# layout.net
KiCad netlist of a schematic drawn in EAGLE
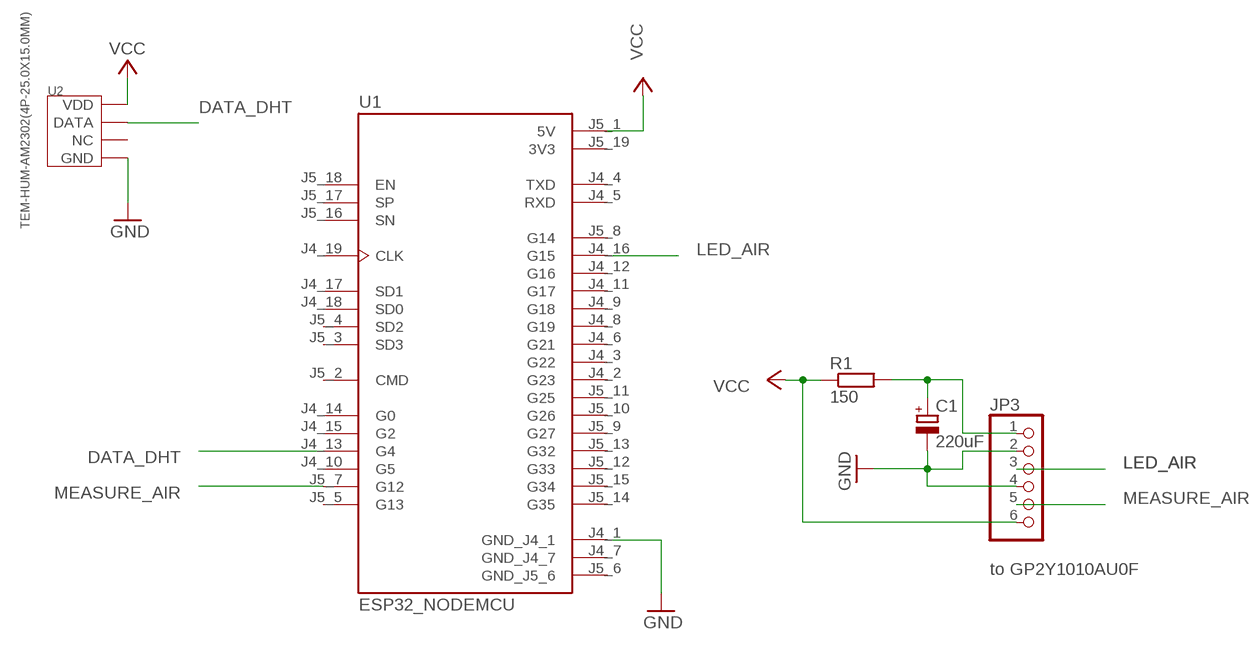
[diagram p0: schematic, sheet 1]

(export (version "E")
  (design (tool "Eeschema 10.0.6"))
  (components
    (comp (ref "C1")
      (value "220uF")
      (footprint "eagle-import:E2-5")
      (libsource (lib "eagle-import") (part "CPOL-EUE2-5"))
    )
    (comp (ref "JP3")
      (value "to GP2Y1010AU0F")
      (footprint "eagle-import:1X06")
      (libsource (lib "eagle-import") (part "PINHD-1X6"))
    )
    (comp (ref "R1")
      (value "150")
      (footprint "eagle-import:0204_7")
      (libsource (lib "eagle-import") (part "R-EU_0204/7"))
    )
    (comp (ref "U1")
      (value "ESP32_NODEMCU")
      (footprint "eagle-import:MODULE_ESP32_NODEMCU")
      (fields (field (name "MF") "Espressif Systems") (field (name "MP") "ESP32 NodeMCU"))
      (libsource (lib "eagle-import") (part "ESP32_NODEMCU"))
    )
    (comp (ref "U2")
      (value "TEM-HUM-AM2302(4P-25.0X15.0MM)")
      (footprint "eagle-import:SNR4-2.54-25.0X15.0X7.0MM")
      (fields (field (name "MF") "MCM Electronics") (field (name "MP") "AM2302"))
      (libsource (lib "eagle-import") (part "TEM-HUM-AM2302(4P-25.0X15.0MM)"))
    )
  )
  (nets
    (net (code "1") (name "/3V3") (class "Default")
      (node (ref "U1") (pin "J5_19") (pinfunction "3V3_J5_19") (pintype "power_in"))
    )
    (net (code "2") (name "/DATA_DHT") (class "Default")
      (node (ref "U1") (pin "J4_13") (pinfunction "G4_J4_13") (pintype "bidirectional"))
      (node (ref "U2") (pin "P$2") (pinfunction "DATA_P$2") (pintype "bidirectional"))
    )
    (net (code "3") (name "/GND_J4_7") (class "Default")
      (node (ref "U1") (pin "J4_7") (pinfunction "GND_J4_7_J4_7") (pintype "power_in"))
    )
    (net (code "4") (name "/GND_J5_6") (class "Default")
      (node (ref "U1") (pin "J5_6") (pinfunction "GND_J5_6_J5_6") (pintype "power_in"))
    )
    (net (code "5") (name "/LED_AIR") (class "Default")
      (node (ref "JP3") (pin "3") (pinfunction "3_3") (pintype "passive"))
      (node (ref "U1") (pin "J4_16") (pinfunction "G15_J4_16") (pintype "bidirectional"))
    )
    (net (code "6") (name "/MEASURE_AIR") (class "Default")
      (node (ref "JP3") (pin "5") (pinfunction "5_5") (pintype "passive"))
      (node (ref "U1") (pin "J5_7") (pinfunction "G12_J5_7") (pintype "bidirectional"))
    )
    (net (code "7") (name "GND") (class "Default")
      (node (ref "C1") (pin "-") (pinfunction "-_-") (pintype "passive"))
      (node (ref "JP3") (pin "2") (pinfunction "2_2") (pintype "passive"))
      (node (ref "JP3") (pin "4") (pinfunction "4_4") (pintype "passive"))
      (node (ref "U1") (pin "J4_1") (pinfunction "GND_J4_1_J4_1") (pintype "power_in"))
      (node (ref "U2") (pin "P$4") (pinfunction "GND_P$4") (pintype "power_in"))
    )
    (net (code "8") (name "Net-(C1-Pad+)") (class "Default")
      (node (ref "C1") (pin "+") (pinfunction "+_+") (pintype "passive"))
      (node (ref "JP3") (pin "1") (pinfunction "1_1") (pintype "passive"))
      (node (ref "R1") (pin "2") (pinfunction "2_2") (pintype "passive"))
    )
    (net (code "9") (name "VCC") (class "Default")
      (node (ref "JP3") (pin "6") (pinfunction "6_6") (pintype "passive"))
      (node (ref "R1") (pin "1") (pinfunction "1_1") (pintype "passive"))
      (node (ref "U1") (pin "J5_1") (pinfunction "5V_J5_1") (pintype "power_in"))
      (node (ref "U2") (pin "P$1") (pinfunction "VDD_P$1") (pintype "power_in"))
    )
    (net (code "10") (name "unconnected-(U1-CLK-PadJ4_19)") (class "Default")
      (node (ref "U1") (pin "J4_19") (pinfunction "CLK_J4_19") (pintype "input"))
    )
    (net (code "11") (name "unconnected-(U1-CMD-PadJ5_2)") (class "Default")
      (node (ref "U1") (pin "J5_2") (pinfunction "CMD_J5_2") (pintype "bidirectional"))
    )
    (net (code "12") (name "unconnected-(U1-EN-PadJ5_18)") (class "Default")
      (node (ref "U1") (pin "J5_18") (pinfunction "EN_J5_18") (pintype "input"))
    )
    (net (code "13") (name "unconnected-(U1-G0-PadJ4_14)") (class "Default")
      (node (ref "U1") (pin "J4_14") (pinfunction "G0_J4_14") (pintype "bidirectional"))
    )
    (net (code "14") (name "unconnected-(U1-G2-PadJ4_15)") (class "Default")
      (node (ref "U1") (pin "J4_15") (pinfunction "G2_J4_15") (pintype "bidirectional"))
    )
    (net (code "15") (name "unconnected-(U1-G5-PadJ4_10)") (class "Default")
      (node (ref "U1") (pin "J4_10") (pinfunction "G5_J4_10") (pintype "bidirectional"))
    )
    (net (code "16") (name "unconnected-(U1-G13-PadJ5_5)") (class "Default")
      (node (ref "U1") (pin "J5_5") (pinfunction "G13_J5_5") (pintype "bidirectional"))
    )
    (net (code "17") (name "unconnected-(U1-G14-PadJ5_8)") (class "Default")
      (node (ref "U1") (pin "J5_8") (pinfunction "G14_J5_8") (pintype "bidirectional"))
    )
    (net (code "18") (name "unconnected-(U1-G16-PadJ4_12)") (class "Default")
      (node (ref "U1") (pin "J4_12") (pinfunction "G16_J4_12") (pintype "bidirectional"))
    )
    (net (code "19") (name "unconnected-(U1-G17-PadJ4_11)") (class "Default")
      (node (ref "U1") (pin "J4_11") (pinfunction "G17_J4_11") (pintype "bidirectional"))
    )
    (net (code "20") (name "unconnected-(U1-G18-PadJ4_9)") (class "Default")
      (node (ref "U1") (pin "J4_9") (pinfunction "G18_J4_9") (pintype "bidirectional"))
    )
    (net (code "21") (name "unconnected-(U1-G19-PadJ4_8)") (class "Default")
      (node (ref "U1") (pin "J4_8") (pinfunction "G19_J4_8") (pintype "bidirectional"))
    )
    (net (code "22") (name "unconnected-(U1-G21-PadJ4_6)") (class "Default")
      (node (ref "U1") (pin "J4_6") (pinfunction "G21_J4_6") (pintype "bidirectional"))
    )
    (net (code "23") (name "unconnected-(U1-G22-PadJ4_3)") (class "Default")
      (node (ref "U1") (pin "J4_3") (pinfunction "G22_J4_3") (pintype "bidirectional"))
    )
    (net (code "24") (name "unconnected-(U1-G23-PadJ4_2)") (class "Default")
      (node (ref "U1") (pin "J4_2") (pinfunction "G23_J4_2") (pintype "bidirectional"))
    )
    (net (code "25") (name "unconnected-(U1-G25-PadJ5_11)") (class "Default")
      (node (ref "U1") (pin "J5_11") (pinfunction "G25_J5_11") (pintype "bidirectional"))
    )
    (net (code "26") (name "unconnected-(U1-G26-PadJ5_10)") (class "Default")
      (node (ref "U1") (pin "J5_10") (pinfunction "G26_J5_10") (pintype "bidirectional"))
    )
    (net (code "27") (name "unconnected-(U1-G27-PadJ5_9)") (class "Default")
      (node (ref "U1") (pin "J5_9") (pinfunction "G27_J5_9") (pintype "bidirectional"))
    )
    (net (code "28") (name "unconnected-(U1-G32-PadJ5_13)") (class "Default")
      (node (ref "U1") (pin "J5_13") (pinfunction "G32_J5_13") (pintype "bidirectional"))
    )
    (net (code "29") (name "unconnected-(U1-G33-PadJ5_12)") (class "Default")
      (node (ref "U1") (pin "J5_12") (pinfunction "G33_J5_12") (pintype "bidirectional"))
    )
    (net (code "30") (name "unconnected-(U1-G34-PadJ5_15)") (class "Default")
      (node (ref "U1") (pin "J5_15") (pinfunction "G34_J5_15") (pintype "bidirectional"))
    )
    (net (code "31") (name "unconnected-(U1-G35-PadJ5_14)") (class "Default")
      (node (ref "U1") (pin "J5_14") (pinfunction "G35_J5_14") (pintype "bidirectional"))
    )
    (net (code "32") (name "unconnected-(U1-RXD-PadJ4_5)") (class "Default")
      (node (ref "U1") (pin "J4_5") (pinfunction "RXD_J4_5") (pintype "input"))
    )
    (net (code "33") (name "unconnected-(U1-SD0-PadJ4_18)") (class "Default")
      (node (ref "U1") (pin "J4_18") (pinfunction "SD0_J4_18") (pintype "bidirectional"))
    )
    (net (code "34") (name "unconnected-(U1-SD1-PadJ4_17)") (class "Default")
      (node (ref "U1") (pin "J4_17") (pinfunction "SD1_J4_17") (pintype "bidirectional"))
    )
    (net (code "35") (name "unconnected-(U1-SD2-PadJ5_4)") (class "Default")
      (node (ref "U1") (pin "J5_4") (pinfunction "SD2_J5_4") (pintype "bidirectional"))
    )
    (net (code "36") (name "unconnected-(U1-SD3-PadJ5_3)") (class "Default")
      (node (ref "U1") (pin "J5_3") (pinfunction "SD3_J5_3") (pintype "bidirectional"))
    )
    (net (code "37") (name "unconnected-(U1-SN-PadJ5_16)") (class "Default")
      (node (ref "U1") (pin "J5_16") (pinfunction "SN_J5_16") (pintype "input"))
    )
    (net (code "38") (name "unconnected-(U1-SP-PadJ5_17)") (class "Default")
      (node (ref "U1") (pin "J5_17") (pinfunction "SP_J5_17") (pintype "input"))
    )
    (net (code "39") (name "unconnected-(U1-TXD-PadJ4_4)") (class "Default")
      (node (ref "U1") (pin "J4_4") (pinfunction "TXD_J4_4") (pintype "output"))
    )
    (net (code "40") (name "unconnected-(U2-NC-PadP$3)") (class "Default")
      (node (ref "U2") (pin "P$3") (pinfunction "NC_P$3") (pintype "no_connect"))
    )
  )
)
